# SUP_1_5_3_3.net
KiCad netlist of a schematic drawn in Altium Designer
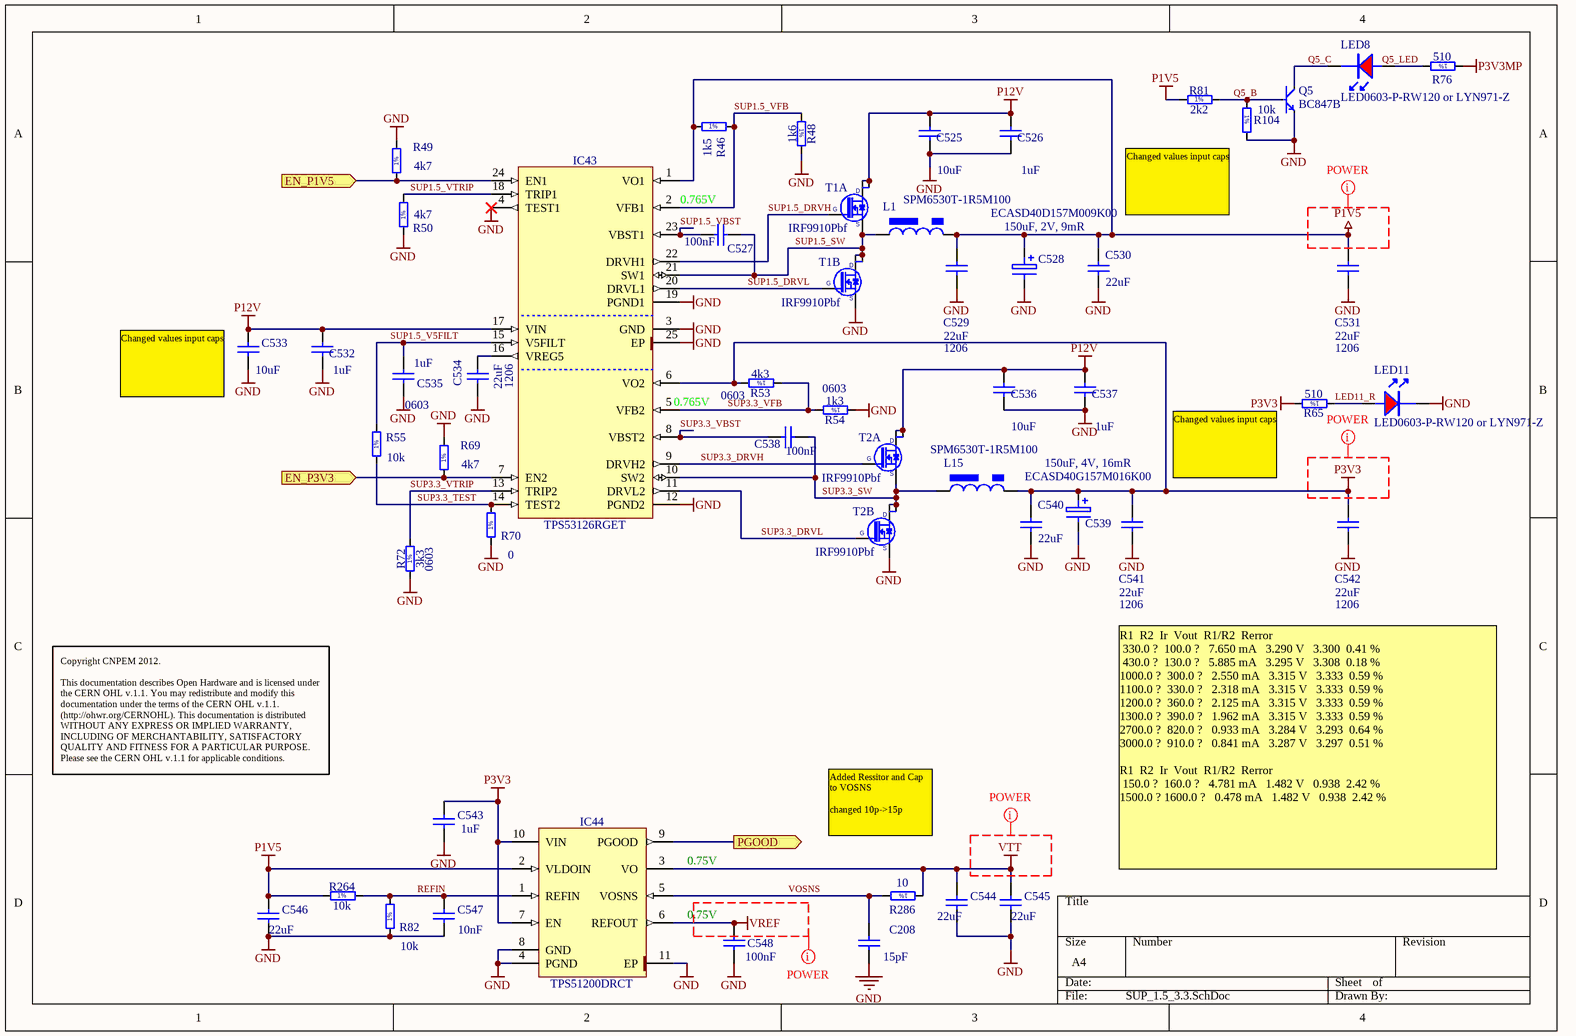
[diagram p0: SUP_1.5_3.3.SchDoc]

(export (version "E")
  (design (tool "Eeschema 10.0.6"))
  (components
    (comp (ref "C208")
      (value "15pF")
      (footprint "CAPC1005X55N")
      (description "Non-polarised capacitor")
      (fields
        (field (name "PART NUMBER") "CC0402_15PF_50V_5%_NP0")
        (field (name "VOLTAGE") "50V")
        (field (name "AUTHOR") "CERN DEM JLC")
      )
      (libsource (lib "Capacitors") (part "Capacitor - non polarized"))
    )
    (comp (ref "C525")
      (value "10uF")
      (footprint "CAPC2012X135N")
      (description "Non-polarised capacitor")
      (fields
        (field (name "PART NUMBER") "CC0805_10UF_16V_10%_X5R")
        (field (name "VOLTAGE") "16V")
        (field (name "AUTHOR") "CERN DEM JLC")
      )
      (libsource (lib "Capacitors") (part "Capacitor - non polarized"))
    )
    (comp (ref "C526")
      (value "1uF")
      (footprint "CAPC1608X87N")
      (description "Non-polarised capacitor")
      (fields
        (field (name "PART NUMBER") "CC0603_1UF_16V_10%_X7R")
        (field (name "VOLTAGE") "16V")
        (field (name "AUTHOR") "CERN DEM JLC")
      )
      (libsource (lib "Capacitors") (part "Capacitor - non polarized"))
    )
    (comp (ref "C527")
      (value "100nF")
      (footprint "CAPC1005X55N")
      (description "Non-polarised capacitor")
      (fields
        (field (name "PART NUMBER") "CC0402_100NF_16V_10%_X7R")
        (field (name "VOLTAGE") "16V")
        (field (name "AUTHOR") "CERN DEM JLC")
      )
      (libsource (lib "Capacitors") (part "Capacitor - non polarized"))
    )
    (comp (ref "C528")
      (value "ECASD40D157M009K00")
      (footprint "2917_POLY")
      (description "POLY, 150uF, 2V, ESR: 9mR")
      (fields (field (name "ALTIUM_VALUE") "150uF, 2V, 9mR"))
      (libsource (lib "LIBRARY_SCH") (part "CAP_POLYMER_SMDD"))
    )
    (comp (ref "C529")
      (value "22uF")
      (footprint "CAPC3216X180N")
      (description "Non-polarised capacitor")
      (fields
        (field (name "PART NUMBER") "CC1206_22UF_10V_10%_X7R")
        (field (name "VOLTAGE") "10V")
        (field (name "CASE") "1206")
        (field (name "AUTHOR") "CERN DEM JLC")
      )
      (libsource (lib "Capacitors") (part "Capacitor - non polarized"))
    )
    (comp (ref "C530")
      (value "22uF")
      (footprint "CAPC3216X180N")
      (description "Non-polarised capacitor")
      (fields
        (field (name "PART NUMBER") "CC1206_22UF_10V_10%_X7R")
        (field (name "VOLTAGE") "10V")
        (field (name "AUTHOR") "CERN DEM JLC")
      )
      (libsource (lib "Capacitors") (part "Capacitor - non polarized"))
    )
    (comp (ref "C531")
      (value "22uF")
      (footprint "CAPC3216X180N")
      (description "Non-polarised capacitor")
      (fields
        (field (name "PART NUMBER") "CC1206_22UF_10V_10%_X7R")
        (field (name "VOLTAGE") "10V")
        (field (name "CASE") "1206")
        (field (name "AUTHOR") "CERN DEM JLC")
      )
      (libsource (lib "Capacitors") (part "Capacitor - non polarized"))
    )
    (comp (ref "C532")
      (value "1uF")
      (footprint "CAPC1608X87N")
      (description "Non-polarised capacitor")
      (fields
        (field (name "PART NUMBER") "CC0603_1UF_16V_10%_X7R")
        (field (name "VOLTAGE") "16V")
        (field (name "AUTHOR") "CERN DEM JLC")
      )
      (libsource (lib "Capacitors") (part "Capacitor - non polarized"))
    )
    (comp (ref "C533")
      (value "10uF")
      (footprint "CAPC2012X135N")
      (description "Non-polarised capacitor")
      (fields
        (field (name "PART NUMBER") "CC0805_10UF_16V_10%_X5R")
        (field (name "VOLTAGE") "16V")
        (field (name "AUTHOR") "CERN DEM JLC")
      )
      (libsource (lib "Capacitors") (part "Capacitor - non polarized"))
    )
    (comp (ref "C534")
      (value "22uF")
      (footprint "CAPC3216X180N")
      (description "Non-polarised capacitor")
      (fields
        (field (name "PART NUMBER") "CC1206_22UF_10V_10%_X7R")
        (field (name "VOLTAGE") "10V")
        (field (name "CASE") "1206")
        (field (name "AUTHOR") "CERN DEM JLC")
      )
      (libsource (lib "Capacitors") (part "Capacitor - non polarized"))
    )
    (comp (ref "C535")
      (value "1uF")
      (footprint "CAPC1608X87N")
      (description "Non-polarised capacitor")
      (fields
        (field (name "PART NUMBER") "CC0603_1UF_16V_10%_X7R")
        (field (name "VOLTAGE") "16V")
        (field (name "CASE") "0603")
        (field (name "AUTHOR") "CERN DEM JLC")
      )
      (libsource (lib "Capacitors") (part "Capacitor - non polarized"))
    )
    (comp (ref "C536")
      (value "10uF")
      (footprint "CAPC2012X135N")
      (description "Non-polarised capacitor")
      (fields
        (field (name "PART NUMBER") "CC0805_10UF_16V_10%_X5R")
        (field (name "VOLTAGE") "16V")
        (field (name "AUTHOR") "CERN DEM JLC")
      )
      (libsource (lib "Capacitors") (part "Capacitor - non polarized"))
    )
    (comp (ref "C537")
      (value "1uF")
      (footprint "CAPC1608X87N")
      (description "Non-polarised capacitor")
      (fields
        (field (name "PART NUMBER") "CC0603_1UF_16V_10%_X7R")
        (field (name "VOLTAGE") "16V")
        (field (name "AUTHOR") "CERN DEM JLC")
      )
      (libsource (lib "Capacitors") (part "Capacitor - non polarized"))
    )
    (comp (ref "C538")
      (value "100nF")
      (footprint "CAPC1005X55N")
      (description "Non-polarised capacitor")
      (fields
        (field (name "PART NUMBER") "CC0402_100NF_16V_10%_X7R")
        (field (name "VOLTAGE") "16V")
        (field (name "AUTHOR") "CERN DEM JLC")
      )
      (libsource (lib "Capacitors") (part "Capacitor - non polarized"))
    )
    (comp (ref "C539")
      (value "ECASD40G157M016K00")
      (footprint "2917_POLY")
      (description "POLY, 150uF, 4V, ESR: 16mR")
      (fields (field (name "ALTIUM_VALUE") "150uF, 4V, 16mR"))
      (libsource (lib "LIBRARY_SCH") (part "CAP_POLYMER_SMDD"))
    )
    (comp (ref "C540")
      (value "22uF")
      (footprint "CAPC3216X180N")
      (description "Non-polarised capacitor")
      (fields
        (field (name "PART NUMBER") "CC1206_22UF_10V_10%_X7R")
        (field (name "VOLTAGE") "10V")
        (field (name "AUTHOR") "CERN DEM JLC")
      )
      (libsource (lib "Capacitors") (part "Capacitor - non polarized"))
    )
    (comp (ref "C541")
      (value "22uF")
      (footprint "CAPC3216X180N")
      (description "Non-polarised capacitor")
      (fields
        (field (name "PART NUMBER") "CC1206_22UF_10V_10%_X7R")
        (field (name "VOLTAGE") "10V")
        (field (name "CASE") "1206")
        (field (name "AUTHOR") "CERN DEM JLC")
      )
      (libsource (lib "Capacitors") (part "Capacitor - non polarized"))
    )
    (comp (ref "C542")
      (value "22uF")
      (footprint "CAPC3216X180N")
      (description "Non-polarised capacitor")
      (fields
        (field (name "PART NUMBER") "CC1206_22UF_10V_10%_X7R")
        (field (name "VOLTAGE") "10V")
        (field (name "CASE") "1206")
        (field (name "AUTHOR") "CERN DEM JLC")
      )
      (libsource (lib "Capacitors") (part "Capacitor - non polarized"))
    )
    (comp (ref "C543")
      (value "1uF")
      (footprint "CAPC1608X87N")
      (description "Non-polarised capacitor")
      (fields
        (field (name "PART NUMBER") "CC0603_1UF_16V_10%_X7R")
        (field (name "VOLTAGE") "16V")
        (field (name "AUTHOR") "CERN DEM JLC")
      )
      (libsource (lib "Capacitors") (part "Capacitor - non polarized"))
    )
    (comp (ref "C544")
      (value "22uF")
      (footprint "CAPC3216X180N")
      (description "Non-polarised capacitor")
      (fields
        (field (name "PART NUMBER") "CC1206_22UF_10V_10%_X7R")
        (field (name "VOLTAGE") "10V")
        (field (name "AUTHOR") "CERN DEM JLC")
      )
      (libsource (lib "Capacitors") (part "Capacitor - non polarized"))
    )
    (comp (ref "C545")
      (value "22uF")
      (footprint "CAPC3216X180N")
      (description "Non-polarised capacitor")
      (fields
        (field (name "PART NUMBER") "CC1206_22UF_10V_10%_X7R")
        (field (name "VOLTAGE") "10V")
        (field (name "AUTHOR") "CERN DEM JLC")
      )
      (libsource (lib "Capacitors") (part "Capacitor - non polarized"))
    )
    (comp (ref "C546")
      (value "22uF")
      (footprint "CAPC3216X180N")
      (description "Non-polarised capacitor")
      (fields
        (field (name "PART NUMBER") "CC1206_22UF_10V_10%_X7R")
        (field (name "VOLTAGE") "10V")
        (field (name "AUTHOR") "CERN DEM JLC")
      )
      (libsource (lib "Capacitors") (part "Capacitor - non polarized"))
    )
    (comp (ref "C547")
      (value "10nF")
      (footprint "CAPC1005X55N")
      (description "Non-polarised capacitor")
      (fields
        (field (name "PART NUMBER") "CC0402_10NF_16V_10%_X7R")
        (field (name "VOLTAGE") "16V")
        (field (name "AUTHOR") "CERN DEM JLC")
      )
      (libsource (lib "Capacitors") (part "Capacitor - non polarized"))
    )
    (comp (ref "C548")
      (value "100nF")
      (footprint "CAPC0603X33N")
      (description "Non-polarised capacitor")
      (fields
        (field (name "PART NUMBER") "CC0201_100NF_6.3V_10%_X5R")
        (field (name "VOLTAGE") "6.3V")
        (field (name "AUTHOR") "CERN DEM JLC")
      )
      (libsource (lib "Capacitors") (part "Capacitor - non polarized"))
    )
    (comp (ref "IC43")
      (value "TPS53126RGET")
      (footprint "QFN50P400X400X100-25N-S255")
      (description "Dual Synchronous Step-Down Controller For Low Voltage Power Rails")
      (fields (field (name "MANUFACTURER") "TEXAS INSTRUMENTS") (field (name "AUTHOR") "CERN DEM JLC"))
      (libsource (lib "ICs And Semiconductors") (part "TPS53126RGET"))
    )
    (comp (ref "IC44")
      (value "TPS51200DRCT")
      (footprint "SON50P300X300X100-11N-R175X250")
      (description "Sink/Source DDR Termination Regulator")
      (fields (field (name "MANUFACTURER") "TEXAS INSTRUMENTS") (field (name "AUTHOR") "CERN DEM JLC"))
      (libsource (lib "ICs And Semiconductors") (part "TPS51200DRC"))
    )
    (comp (ref "L1")
      (value "SPM6530T-1R5M100")
      (footprint "IND_TDK_SPM6530")
      (description "1.5uH, 20%, 10mR, 11.5A")
      (libsource (lib "LIBRARY_SCH") (part "L_POWER_SPM6530T"))
    )
    (comp (ref "L15")
      (value "SPM6530T-1R5M100")
      (footprint "IND_TDK_SPM6530")
      (description "1.5uH, 20%, 10mR, 11.5A")
      (libsource (lib "LIBRARY_SCH") (part "L_POWER_SPM6530T"))
    )
    (comp (ref "LED8")
      (value "LED0603-P-RW120 or LYN971-Z")
      (footprint "led_0603R")
      (description "LED 0603 red")
      (libsource (lib "LIBRARY_SCH") (part "LED_0603R"))
    )
    (comp (ref "LED11")
      (value "LED0603-P-RW120 or LYN971-Z")
      (footprint "led_0603R")
      (description "LED 0603 red")
      (libsource (lib "LIBRARY_SCH") (part "LED_0603R"))
    )
    (comp (ref "Q5")
      (value "BC847B")
      (footprint "SOT-23")
      (description "Transistor")
      (libsource (lib "LIBRARY_SCH") (part "Q_BC847B"))
    )
    (comp (ref "R46")
      (value "1k5")
      (footprint "RESC1608X55N")
      (description "Resistor - 1%")
      (fields
        (field (name "PART NUMBER") "R0603_1K5_1%_0.1W_100PPM")
        (field (name "POWER") "0.1W")
        (field (name "AUTHOR") "CERN DEM JLC")
      )
      (libsource (lib "Resistors") (part "Resistor - 1%"))
    )
    (comp (ref "R48")
      (value "1k6")
      (footprint "RESC1608X55N")
      (description "Resistor - 1%")
      (fields
        (field (name "PART NUMBER") "R0603_1K6_1%_0.1W_100PPM")
        (field (name "POWER") "0.1W")
        (field (name "AUTHOR") "CERN DEM JLC")
      )
      (libsource (lib "Resistors") (part "Resistor - 1%"))
    )
    (comp (ref "R49")
      (value "4k7")
      (footprint "RESC1005X40N")
      (description "Resistor - 1%")
      (fields
        (field (name "PART NUMBER") "R0402_4K7_1%_0.0625W_100PPM")
        (field (name "POWER") "0.0625W")
        (field (name "AUTHOR") "CERN DEM JLC")
      )
      (libsource (lib "Resistors") (part "Resistor - 1%"))
    )
    (comp (ref "R50")
      (value "4k7")
      (footprint "RESC1005X40N")
      (description "Resistor - 1%")
      (fields
        (field (name "PART NUMBER") "R0402_4K7_1%_0.0625W_100PPM")
        (field (name "POWER") "0.0625W")
        (field (name "AUTHOR") "CERN DEM JLC")
      )
      (libsource (lib "Resistors") (part "Resistor - 1%"))
    )
    (comp (ref "R53")
      (value "4k3")
      (footprint "RESC1608X55N")
      (description "Resistor - 1%")
      (fields
        (field (name "PART NUMBER") "R0603_4K3_1%_0.1W_100PPM")
        (field (name "POWER") "0.1W")
        (field (name "CASE") "0603")
        (field (name "AUTHOR") "CERN DEM JLC")
      )
      (libsource (lib "Resistors") (part "Resistor - 1%"))
    )
    (comp (ref "R54")
      (value "1k3")
      (footprint "RESC1608X55N")
      (description "Resistor - 1%")
      (fields
        (field (name "PART NUMBER") "R0603_1K3_1%_0.1W_100PPM")
        (field (name "POWER") "0.1W")
        (field (name "CASE") "0603")
        (field (name "AUTHOR") "CERN DEM JLC")
      )
      (libsource (lib "Resistors") (part "Resistor - 1%"))
    )
    (comp (ref "R55")
      (value "10k")
      (footprint "RESC1005X40N")
      (description "Resistor - 1%")
      (fields
        (field (name "PART NUMBER") "R0402_10K_1%_0.0625W_100PPM")
        (field (name "POWER") "0.0625W")
        (field (name "AUTHOR") "CERN DEM JLC")
      )
      (libsource (lib "Resistors") (part "Resistor - 1%"))
    )
    (comp (ref "R65")
      (value "510")
      (footprint "RESC1005X40N")
      (description "Resistor - 1%")
      (fields
        (field (name "PART NUMBER") "R0402_510R_1%_0.0625W_100PPM")
        (field (name "POWER") "0.0625W")
        (field (name "AUTHOR") "CERN DEM JLC")
      )
      (libsource (lib "Resistors") (part "Resistor - 1%"))
    )
    (comp (ref "R69")
      (value "4k7")
      (footprint "RESC1005X40N")
      (description "Resistor - 1%")
      (fields
        (field (name "PART NUMBER") "R0402_4K7_1%_0.0625W_100PPM")
        (field (name "POWER") "0.0625W")
        (field (name "AUTHOR") "CERN DEM JLC")
      )
      (libsource (lib "Resistors") (part "Resistor - 1%"))
    )
    (comp (ref "R70")
      (value "0")
      (footprint "RESC1005X40N")
      (description "Resistor - 1%")
      (fields
        (field (name "PART NUMBER") "R0402_0R_JUMPER")
        (field (name "MANUFACTURER") "GENERIC")
        (field (name "AUTHOR") "CERN DEM JLC")
      )
      (libsource (lib "Resistors") (part "Resistor - 1%"))
    )
    (comp (ref "R72")
      (value "3k3")
      (footprint "RESC1608X55N")
      (description "Resistor - 1%")
      (fields
        (field (name "PART NUMBER") "R0603_3K3_1%_0.1W_100PPM")
        (field (name "POWER") "0.1W")
        (field (name "CASE") "0603")
        (field (name "AUTHOR") "CERN DEM JLC")
      )
      (libsource (lib "Resistors") (part "Resistor - 1%"))
    )
    (comp (ref "R76")
      (value "510")
      (footprint "RESC1005X40N")
      (description "Resistor - 1%")
      (fields
        (field (name "PART NUMBER") "R0402_510R_1%_0.0625W_100PPM")
        (field (name "POWER") "0.0625W")
        (field (name "AUTHOR") "CERN DEM JLC")
      )
      (libsource (lib "Resistors") (part "Resistor - 1%"))
    )
    (comp (ref "R81")
      (value "2k2")
      (footprint "RESC1005X40N")
      (description "Resistor - 1%")
      (fields
        (field (name "PART NUMBER") "R0402_2K2_1%_0.0625W_100PPM")
        (field (name "POWER") "0.0625W")
        (field (name "AUTHOR") "CERN DEM JLC")
      )
      (libsource (lib "Resistors") (part "Resistor - 1%"))
    )
    (comp (ref "R82")
      (value "10k")
      (footprint "RESC1005X40N")
      (description "Resistor - 1%")
      (fields
        (field (name "PART NUMBER") "R0402_10K_1%_0.0625W_100PPM")
        (field (name "POWER") "0.0625W")
        (field (name "AUTHOR") "CERN DEM JLC")
      )
      (libsource (lib "Resistors") (part "Resistor - 1%"))
    )
    (comp (ref "R104")
      (value "10k")
      (footprint "RESC1005X40N")
      (description "Resistor - 1%")
      (fields
        (field (name "PART NUMBER") "R0402_10K_1%_0.0625W_100PPM")
        (field (name "POWER") "0.0625W")
        (field (name "AUTHOR") "CERN DEM JLC")
      )
      (libsource (lib "Resistors") (part "Resistor - 1%"))
    )
    (comp (ref "R264")
      (value "10k")
      (footprint "RESC1005X40N")
      (description "Resistor - 1%")
      (fields
        (field (name "PART NUMBER") "R0402_10K_1%_0.0625W_100PPM")
        (field (name "POWER") "0.0625W")
        (field (name "AUTHOR") "CERN DEM JLC")
      )
      (libsource (lib "Resistors") (part "Resistor - 1%"))
    )
    (comp (ref "R286")
      (value "10")
      (footprint "RESC1005X40N")
      (description "Resistor - 1%")
      (fields
        (field (name "PART NUMBER") "R0402_10R_1%_0.0625W_200PPM")
        (field (name "POWER") "0.0625W")
        (field (name "AUTHOR") "CERN DEM JLC")
      )
      (libsource (lib "Resistors") (part "Resistor - 1%"))
    )
    (comp (ref "T1")
      (value "IRF9910Pbf")
      (footprint "SOIC127P600X175-8N")
      (description "Dual SO-8 MOSFET For POL Cconverter")
      (fields (field (name "MANUFACTURER") "INTERNATIONAL RECTIFIER") (field (name "AUTHOR") "CERN DEM JLC"))
      (libsource (lib "ICs And Semiconductors") (part "IRF9910"))
    )
    (comp (ref "T2")
      (value "IRF9910Pbf")
      (footprint "SOIC127P600X175-8N")
      (description "Dual SO-8 MOSFET For POL Cconverter")
      (fields (field (name "MANUFACTURER") "INTERNATIONAL RECTIFIER") (field (name "AUTHOR") "CERN DEM JLC"))
      (libsource (lib "ICs And Semiconductors") (part "IRF9910"))
    )
  )
  (nets
    (net (code "1") (name "/EN_P1V5") (class "Default")
      (node (ref "IC43") (pin "24") (pinfunction "EN1_24") (pintype "input"))
      (node (ref "R49") (pin "1") (pinfunction "1_1") (pintype "passive"))
    )
    (net (code "2") (name "/EN_P3V3") (class "Default")
      (node (ref "IC43") (pin "7") (pinfunction "EN2_7") (pintype "input"))
      (node (ref "R69") (pin "1") (pinfunction "1_1") (pintype "passive"))
    )
    (net (code "3") (name "/LED11_R") (class "Default")
      (node (ref "LED11") (pin "A") (pinfunction "A_A") (pintype "passive"))
      (node (ref "R65") (pin "1") (pinfunction "1_1") (pintype "passive"))
    )
    (net (code "4") (name "/PGOOD") (class "Default")
      (node (ref "IC44") (pin "9") (pinfunction "PGOOD_9") (pintype "output"))
    )
    (net (code "5") (name "/Q5_B") (class "Default")
      (node (ref "Q5") (pin "1") (pinfunction "B_1") (pintype "passive"))
      (node (ref "R104") (pin "1") (pinfunction "1_1") (pintype "passive"))
      (node (ref "R81") (pin "2") (pinfunction "2_2") (pintype "passive"))
    )
    (net (code "6") (name "/Q5_C") (class "Default")
      (node (ref "LED8") (pin "K") (pinfunction "K_K") (pintype "passive"))
      (node (ref "Q5") (pin "3") (pinfunction "C_3") (pintype "passive"))
    )
    (net (code "8") (name "/REFIN") (class "Default")
      (node (ref "C547") (pin "2") (pinfunction "2_2") (pintype "passive"))
      (node (ref "IC44") (pin "1") (pinfunction "REFIN_1") (pintype "input"))
      (node (ref "R264") (pin "2") (pinfunction "2_2") (pintype "passive"))
      (node (ref "R82") (pin "2") (pinfunction "2_2") (pintype "passive"))
    )
    (net (code "9") (name "/SUP1.5_DRVH") (class "Default")
      (node (ref "IC43") (pin "22") (pinfunction "DRVH1_22") (pintype "output"))
      (node (ref "T1") (pin "4") (pinfunction "G_4") (pintype "passive"))
    )
    (net (code "10") (name "/SUP1.5_DRVL") (class "Default")
      (node (ref "IC43") (pin "20") (pinfunction "DRVL1_20") (pintype "output"))
      (node (ref "T1") (pin "2") (pinfunction "G_2") (pintype "passive"))
    )
    (net (code "11") (name "/SUP1.5_SW") (class "Default")
      (node (ref "C527") (pin "1") (pinfunction "1_1") (pintype "passive"))
      (node (ref "IC43") (pin "21") (pinfunction "SW1_21") (pintype "bidirectional"))
      (node (ref "L1") (pin "1") (pintype "passive"))
      (node (ref "T1") (pin "3") (pinfunction "S_3") (pintype "passive"))
      (node (ref "T1") (pin "7") (pinfunction "D_7") (pintype "passive"))
      (node (ref "T1") (pin "8") (pinfunction "D_8") (pintype "passive"))
    )
    (net (code "12") (name "/SUP1.5_V5FILT") (class "Default")
      (node (ref "C535") (pin "2") (pinfunction "2_2") (pintype "passive"))
      (node (ref "IC43") (pin "15") (pinfunction "V5FILT_15") (pintype "input"))
      (node (ref "R55") (pin "2") (pinfunction "2_2") (pintype "passive"))
    )
    (net (code "13") (name "/SUP1.5_VBST") (class "Default")
      (node (ref "C527") (pin "2") (pinfunction "2_2") (pintype "passive"))
      (node (ref "IC43") (pin "23") (pinfunction "VBST1_23") (pintype "input"))
    )
    (net (code "14") (name "/SUP1.5_VFB") (class "Default")
      (node (ref "IC43") (pin "2") (pinfunction "VFB1_2") (pintype "input"))
      (node (ref "R46") (pin "2") (pinfunction "2_2") (pintype "passive"))
      (node (ref "R48") (pin "1") (pinfunction "1_1") (pintype "passive"))
    )
    (net (code "15") (name "/SUP1.5_VTRIP") (class "Default")
      (node (ref "IC43") (pin "18") (pinfunction "TRIP1_18") (pintype "input"))
      (node (ref "R50") (pin "2") (pinfunction "2_2") (pintype "passive"))
    )
    (net (code "16") (name "/SUP3.3_DRVH") (class "Default")
      (node (ref "IC43") (pin "9") (pinfunction "DRVH2_9") (pintype "output"))
      (node (ref "T2") (pin "4") (pinfunction "G_4") (pintype "passive"))
    )
    (net (code "17") (name "/SUP3.3_DRVL") (class "Default")
      (node (ref "IC43") (pin "11") (pinfunction "DRVL2_11") (pintype "output"))
      (node (ref "T2") (pin "2") (pinfunction "G_2") (pintype "passive"))
    )
    (net (code "18") (name "/SUP3.3_SW") (class "Default")
      (node (ref "C538") (pin "1") (pinfunction "1_1") (pintype "passive"))
      (node (ref "IC43") (pin "10") (pinfunction "SW2_10") (pintype "bidirectional"))
      (node (ref "L15") (pin "1") (pintype "passive"))
      (node (ref "T2") (pin "3") (pinfunction "S_3") (pintype "passive"))
      (node (ref "T2") (pin "7") (pinfunction "D_7") (pintype "passive"))
      (node (ref "T2") (pin "8") (pinfunction "D_8") (pintype "passive"))
    )
    (net (code "19") (name "/SUP3.3_TEST") (class "Default")
      (node (ref "IC43") (pin "14") (pinfunction "TEST2_14") (pintype "input"))
      (node (ref "R55") (pin "1") (pinfunction "1_1") (pintype "passive"))
      (node (ref "R70") (pin "2") (pinfunction "2_2") (pintype "passive"))
    )
    (net (code "20") (name "/SUP3.3_VBST") (class "Default")
      (node (ref "C538") (pin "2") (pinfunction "2_2") (pintype "passive"))
      (node (ref "IC43") (pin "8") (pinfunction "VBST2_8") (pintype "input"))
    )
    (net (code "21") (name "/SUP3.3_VFB") (class "Default")
      (node (ref "IC43") (pin "5") (pinfunction "VFB2_5") (pintype "input"))
      (node (ref "R53") (pin "1") (pinfunction "1_1") (pintype "passive"))
      (node (ref "R54") (pin "2") (pinfunction "2_2") (pintype "passive"))
    )
    (net (code "22") (name "/SUP3.3_VTRIP") (class "Default")
      (node (ref "IC43") (pin "13") (pinfunction "TRIP2_13") (pintype "input"))
      (node (ref "R72") (pin "2") (pinfunction "2_2") (pintype "passive"))
    )
    (net (code "23") (name "/VOSNS") (class "Default")
      (node (ref "C208") (pin "1") (pinfunction "1_1") (pintype "passive"))
      (node (ref "IC44") (pin "5") (pinfunction "VOSNS_5") (pintype "input"))
      (node (ref "R286") (pin "2") (pinfunction "2_2") (pintype "passive"))
    )
    (net (code "24") (name "GND") (class "Default")
      (node (ref "C208") (pin "2") (pinfunction "2_2") (pintype "passive"))
      (node (ref "C525") (pin "1") (pinfunction "1_1") (pintype "passive"))
      (node (ref "C526") (pin "1") (pinfunction "1_1") (pintype "passive"))
      (node (ref "C528") (pin "2") (pinfunction "2_2") (pintype "passive"))
      (node (ref "C529") (pin "2") (pinfunction "2_2") (pintype "passive"))
      (node (ref "C530") (pin "2") (pinfunction "2_2") (pintype "passive"))
      (node (ref "C531") (pin "2") (pinfunction "2_2") (pintype "passive"))
      (node (ref "C532") (pin "1") (pinfunction "1_1") (pintype "passive"))
      (node (ref "C533") (pin "1") (pinfunction "1_1") (pintype "passive"))
      (node (ref "C534") (pin "1") (pinfunction "1_1") (pintype "passive"))
      (node (ref "C535") (pin "1") (pinfunction "1_1") (pintype "passive"))
      (node (ref "C536") (pin "1") (pinfunction "1_1") (pintype "passive"))
      (node (ref "C537") (pin "1") (pinfunction "1_1") (pintype "passive"))
      (node (ref "C539") (pin "2") (pinfunction "2_2") (pintype "passive"))
      (node (ref "C540") (pin "2") (pinfunction "2_2") (pintype "passive"))
      (node (ref "C541") (pin "2") (pinfunction "2_2") (pintype "passive"))
      (node (ref "C542") (pin "2") (pinfunction "2_2") (pintype "passive"))
      (node (ref "C543") (pin "1") (pinfunction "1_1") (pintype "passive"))
      (node (ref "C544") (pin "1") (pinfunction "1_1") (pintype "passive"))
      (node (ref "C545") (pin "1") (pinfunction "1_1") (pintype "passive"))
      (node (ref "C546") (pin "1") (pinfunction "1_1") (pintype "passive"))
      (node (ref "C547") (pin "1") (pinfunction "1_1") (pintype "passive"))
      (node (ref "C548") (pin "1") (pinfunction "1_1") (pintype "passive"))
      (node (ref "IC43") (pin "12") (pinfunction "PGND2_12") (pintype "power_in"))
      (node (ref "IC43") (pin "19") (pinfunction "PGND1_19") (pintype "power_in"))
      (node (ref "IC43") (pin "25") (pinfunction "EP_25") (pintype "power_in"))
      (node (ref "IC43") (pin "3") (pinfunction "GND_3") (pintype "power_in"))
      (node (ref "IC43") (pin "4") (pinfunction "TEST1_4") (pintype "output"))
      (node (ref "IC44") (pin "11") (pinfunction "EP_11") (pintype "power_in"))
      (node (ref "IC44") (pin "4") (pinfunction "PGND_4") (pintype "power_in"))
      (node (ref "IC44") (pin "8") (pinfunction "GND_8") (pintype "power_in"))
      (node (ref "LED11") (pin "K") (pinfunction "K_K") (pintype "passive"))
      (node (ref "Q5") (pin "2") (pinfunction "E_2") (pintype "passive"))
      (node (ref "R104") (pin "2") (pinfunction "2_2") (pintype "passive"))
      (node (ref "R48") (pin "2") (pinfunction "2_2") (pintype "passive"))
      (node (ref "R49") (pin "2") (pinfunction "2_2") (pintype "passive"))
      (node (ref "R50") (pin "1") (pinfunction "1_1") (pintype "passive"))
      (node (ref "R54") (pin "1") (pinfunction "1_1") (pintype "passive"))
      (node (ref "R69") (pin "2") (pinfunction "2_2") (pintype "passive"))
      (node (ref "R70") (pin "1") (pinfunction "1_1") (pintype "passive"))
      (node (ref "R72") (pin "1") (pinfunction "1_1") (pintype "passive"))
      (node (ref "R82") (pin "1") (pinfunction "1_1") (pintype "passive"))
      (node (ref "T1") (pin "1") (pinfunction "S_1") (pintype "passive"))
      (node (ref "T2") (pin "1") (pinfunction "S_1") (pintype "passive"))
    )
    (net (code "25") (name "Net-(IC43-VREG5)") (class "Default")
      (node (ref "C534") (pin "2") (pinfunction "2_2") (pintype "passive"))
      (node (ref "IC43") (pin "16") (pinfunction "VREG5_16") (pintype "output"))
    )
    (net (code "26") (name "Net-(LED8-PadA)") (class "Default")
      (node (ref "LED8") (pin "A") (pinfunction "A_A") (pintype "passive"))
      (node (ref "R76") (pin "2") (pinfunction "2_2") (pintype "passive"))
    )
    (net (code "27") (name "P1V5") (class "Default")
      (node (ref "C528") (pin "1") (pinfunction "1_1") (pintype "passive"))
      (node (ref "C529") (pin "1") (pinfunction "1_1") (pintype "passive"))
      (node (ref "C530") (pin "1") (pinfunction "1_1") (pintype "passive"))
      (node (ref "C531") (pin "1") (pinfunction "1_1") (pintype "passive"))
      (node (ref "C546") (pin "2") (pinfunction "2_2") (pintype "passive"))
      (node (ref "IC43") (pin "1") (pinfunction "VO1_1") (pintype "input"))
      (node (ref "IC44") (pin "2") (pinfunction "VLDOIN_2") (pintype "input"))
      (node (ref "L1") (pin "2") (pintype "passive"))
      (node (ref "R264") (pin "1") (pinfunction "1_1") (pintype "passive"))
      (node (ref "R46") (pin "1") (pinfunction "1_1") (pintype "passive"))
      (node (ref "R81") (pin "1") (pinfunction "1_1") (pintype "passive"))
    )
    (net (code "28") (name "P3V3") (class "Default")
      (node (ref "C539") (pin "1") (pinfunction "1_1") (pintype "passive"))
      (node (ref "C540") (pin "1") (pinfunction "1_1") (pintype "passive"))
      (node (ref "C541") (pin "1") (pinfunction "1_1") (pintype "passive"))
      (node (ref "C542") (pin "1") (pinfunction "1_1") (pintype "passive"))
      (node (ref "C543") (pin "2") (pinfunction "2_2") (pintype "passive"))
      (node (ref "IC43") (pin "6") (pinfunction "VO2_6") (pintype "input"))
      (node (ref "IC44") (pin "10") (pinfunction "VIN_10") (pintype "power_in"))
      (node (ref "IC44") (pin "7") (pinfunction "EN_7") (pintype "input"))
      (node (ref "L15") (pin "2") (pintype "passive"))
      (node (ref "R53") (pin "2") (pinfunction "2_2") (pintype "passive"))
      (node (ref "R65") (pin "2") (pinfunction "2_2") (pintype "passive"))
    )
    (net (code "29") (name "P3V3MP") (class "Default")
      (node (ref "R76") (pin "1") (pinfunction "1_1") (pintype "passive"))
    )
    (net (code "30") (name "P12V") (class "Default")
      (node (ref "C525") (pin "2") (pinfunction "2_2") (pintype "passive"))
      (node (ref "C526") (pin "2") (pinfunction "2_2") (pintype "passive"))
      (node (ref "C532") (pin "2") (pinfunction "2_2") (pintype "passive"))
      (node (ref "C533") (pin "2") (pinfunction "2_2") (pintype "passive"))
      (node (ref "C536") (pin "2") (pinfunction "2_2") (pintype "passive"))
      (node (ref "C537") (pin "2") (pinfunction "2_2") (pintype "passive"))
      (node (ref "IC43") (pin "17") (pinfunction "VIN_17") (pintype "input"))
      (node (ref "T1") (pin "5") (pinfunction "D_5") (pintype "passive"))
      (node (ref "T1") (pin "6") (pinfunction "D_6") (pintype "passive"))
      (node (ref "T2") (pin "5") (pinfunction "D_5") (pintype "passive"))
      (node (ref "T2") (pin "6") (pinfunction "D_6") (pintype "passive"))
    )
    (net (code "31") (name "VREF") (class "Default")
      (node (ref "C548") (pin "2") (pinfunction "2_2") (pintype "passive"))
      (node (ref "IC44") (pin "6") (pinfunction "REFOUT_6") (pintype "output"))
    )
    (net (code "32") (name "VTT") (class "Default")
      (node (ref "C544") (pin "2") (pinfunction "2_2") (pintype "passive"))
      (node (ref "C545") (pin "2") (pinfunction "2_2") (pintype "passive"))
      (node (ref "IC44") (pin "3") (pinfunction "VO_3") (pintype "power_in"))
      (node (ref "R286") (pin "1") (pinfunction "1_1") (pintype "passive"))
    )
  )
)
